# Target.net
KiCad netlist of a schematic drawn in EAGLE
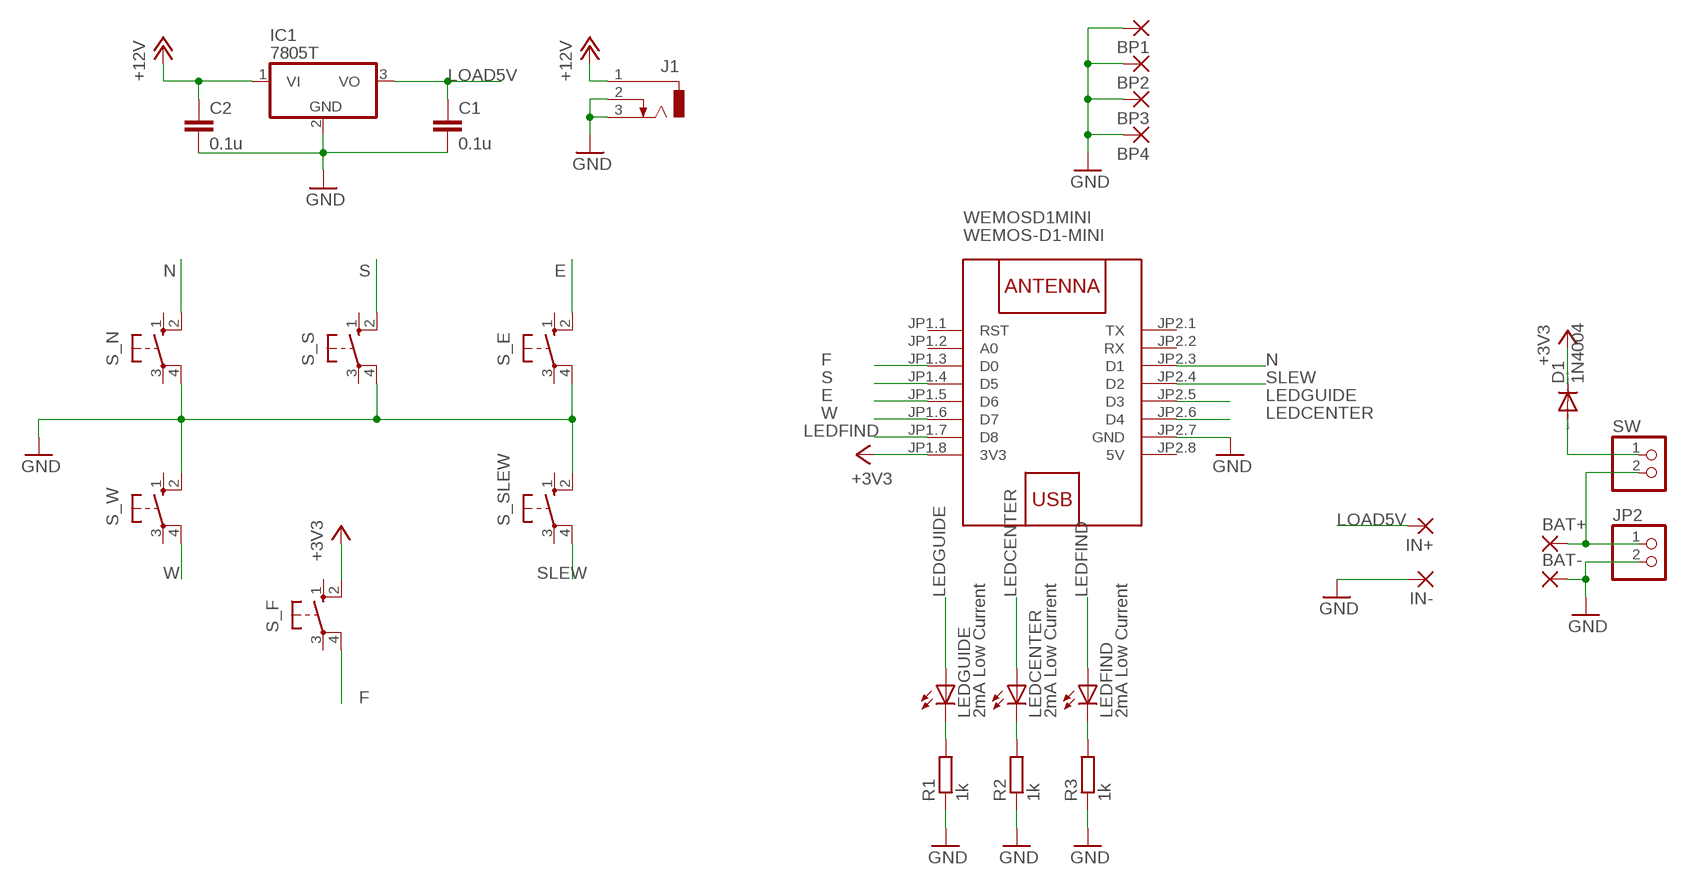
[diagram p0: schematic, sheet 1]

(export (version "E")
  (design (tool "Eeschema 10.0.6"))
  (components
    (comp (ref "BAT+")
      (value "2,15/1,0")
      (footprint "eagle-import:2,15_1,0")
      (libsource (lib "eagle-import") (part "2,15/1,0"))
    )
    (comp (ref "BAT-")
      (value "2,15/1,0")
      (footprint "eagle-import:2,15_1,0")
      (libsource (lib "eagle-import") (part "2,15/1,0"))
    )
    (comp (ref "BP1")
      (value "3,81/1,4")
      (footprint "eagle-import:3,81_1,4")
      (libsource (lib "eagle-import") (part "3,81/1,4"))
    )
    (comp (ref "BP2")
      (value "3,81/1,4")
      (footprint "eagle-import:3,81_1,4")
      (libsource (lib "eagle-import") (part "3,81/1,4"))
    )
    (comp (ref "BP3")
      (value "3,81/1,4")
      (footprint "eagle-import:3,81_1,4")
      (libsource (lib "eagle-import") (part "3,81/1,4"))
    )
    (comp (ref "BP4")
      (value "3,81/1,4")
      (footprint "eagle-import:3,81_1,4")
      (libsource (lib "eagle-import") (part "3,81/1,4"))
    )
    (comp (ref "C1")
      (value "0.1u")
      (footprint "eagle-import:C025_050-025X075")
      (libsource (lib "eagle-import") (part "C-EU025_050-025X075"))
    )
    (comp (ref "C2")
      (value "0.1u")
      (footprint "eagle-import:C025_050-025X075")
      (libsource (lib "eagle-import") (part "C-EU025_050-025X075"))
    )
    (comp (ref "D1")
      (value "1N4004")
      (footprint "eagle-import:DO41-10")
      (libsource (lib "eagle-import") (part "1N4004"))
    )
    (comp (ref "IC1")
      (value "7805T")
      (footprint "eagle-import:TO220H")
      (libsource (lib "eagle-import") (part "78T05"))
    )
    (comp (ref "IN+")
      (value "2,15/1,0")
      (footprint "eagle-import:2,15_1,0")
      (libsource (lib "eagle-import") (part "2,15/1,0"))
    )
    (comp (ref "IN-")
      (value "2,15/1,0")
      (footprint "eagle-import:2,15_1,0")
      (libsource (lib "eagle-import") (part "2,15/1,0"))
    )
    (comp (ref "J1")
      (value "DCJ0303")
      (footprint "eagle-import:DCJ0303")
      (libsource (lib "eagle-import") (part "DCJ0303"))
    )
    (comp (ref "JP2")
      (value "PINHD-1X2")
      (footprint "eagle-import:1X02")
      (libsource (lib "eagle-import") (part "PINHD-1X2"))
    )
    (comp (ref "LEDCENTER")
      (value "2mA Low Current")
      (footprint "eagle-import:LED3MM")
      (libsource (lib "eagle-import") (part "LED3MM"))
    )
    (comp (ref "LEDFIND")
      (value "2mA Low Current")
      (footprint "eagle-import:LED3MM")
      (libsource (lib "eagle-import") (part "LED3MM"))
    )
    (comp (ref "LEDGUIDE")
      (value "2mA Low Current")
      (footprint "eagle-import:LED3MM")
      (libsource (lib "eagle-import") (part "LED3MM"))
    )
    (comp (ref "R1")
      (value "1k")
      (footprint "eagle-import:0204_7")
      (libsource (lib "eagle-import") (part "R-EU_0204/7"))
    )
    (comp (ref "R2")
      (value "1k")
      (footprint "eagle-import:0204_7")
      (libsource (lib "eagle-import") (part "R-EU_0204/7"))
    )
    (comp (ref "R3")
      (value "1k")
      (footprint "eagle-import:0204_7")
      (libsource (lib "eagle-import") (part "R-EU_0204/7"))
    )
    (comp (ref "SW")
      (value "PINHD-1X2")
      (footprint "eagle-import:1X02")
      (libsource (lib "eagle-import") (part "PINHD-1X2"))
    )
    (comp (ref "S_E")
      (value "40-XX")
      (footprint "eagle-import:B3F-40XX")
      (fields (field (name "MF") "OMRON COMPONENTS USA") (field (name "MPN") "B3F-4000"))
      (libsource (lib "eagle-import") (part "40-XX"))
    )
    (comp (ref "S_F")
      (value "40-XX")
      (footprint "eagle-import:B3F-40XX")
      (fields (field (name "MF") "OMRON COMPONENTS USA") (field (name "MPN") "B3F-4000"))
      (libsource (lib "eagle-import") (part "40-XX"))
    )
    (comp (ref "S_N")
      (value "40-XX")
      (footprint "eagle-import:B3F-40XX")
      (fields (field (name "MF") "OMRON COMPONENTS USA") (field (name "MPN") "B3F-4000"))
      (libsource (lib "eagle-import") (part "40-XX"))
    )
    (comp (ref "S_S")
      (value "40-XX")
      (footprint "eagle-import:B3F-40XX")
      (fields (field (name "MF") "OMRON COMPONENTS USA") (field (name "MPN") "B3F-4000"))
      (libsource (lib "eagle-import") (part "40-XX"))
    )
    (comp (ref "S_SLEW")
      (value "40-XX")
      (footprint "eagle-import:B3F-40XX")
      (fields (field (name "MF") "OMRON COMPONENTS USA") (field (name "MPN") "B3F-4000"))
      (libsource (lib "eagle-import") (part "40-XX"))
    )
    (comp (ref "S_W")
      (value "40-XX")
      (footprint "eagle-import:B3F-40XX")
      (fields (field (name "MF") "OMRON COMPONENTS USA") (field (name "MPN") "B3F-4000"))
      (libsource (lib "eagle-import") (part "40-XX"))
    )
    (comp (ref "WEMOSD1MINI")
      (value "WEMOS-D1-MINI")
      (footprint "eagle-import:WEMOS-D1-MINI")
      (libsource (lib "eagle-import") (part "WEMOS-D1-MINI"))
    )
  )
  (nets
    (net (code "1") (name "+3V3") (class "Default")
      (node (ref "D1") (pin "C") (pinfunction "C_C") (pintype "passive"))
      (node (ref "S_F") (pin "2") (pinfunction "S1_2") (pintype "passive"))
      (node (ref "WEMOSD1MINI") (pin "JP1.8") (pinfunction "3V3_JP1.8") (pintype "power_in"))
    )
    (net (code "2") (name "+12V") (class "Default")
      (node (ref "C2") (pin "1") (pinfunction "1_1") (pintype "passive"))
      (node (ref "IC1") (pin "1") (pinfunction "VI_1") (pintype "input"))
      (node (ref "J1") (pin "1") (pinfunction "1_1") (pintype "passive"))
    )
    (net (code "3") (name "/5V") (class "Default")
      (node (ref "WEMOSD1MINI") (pin "JP2.8") (pinfunction "5V_JP2.8") (pintype "power_in"))
    )
    (net (code "4") (name "/E") (class "Default")
      (node (ref "S_E") (pin "2") (pinfunction "S1_2") (pintype "passive"))
      (node (ref "WEMOSD1MINI") (pin "JP1.5") (pinfunction "D6_JP1.5") (pintype "bidirectional"))
    )
    (net (code "5") (name "/F") (class "Default")
      (node (ref "S_F") (pin "4") (pinfunction "P1_4") (pintype "passive"))
      (node (ref "WEMOSD1MINI") (pin "JP1.3") (pinfunction "D0_JP1.3") (pintype "bidirectional"))
    )
    (net (code "6") (name "/LEDCENTER") (class "Default")
      (node (ref "LEDCENTER") (pin "A") (pinfunction "A_A") (pintype "passive"))
      (node (ref "WEMOSD1MINI") (pin "JP2.6") (pinfunction "D4_JP2.6") (pintype "bidirectional"))
    )
    (net (code "7") (name "/LEDFIND") (class "Default")
      (node (ref "LEDFIND") (pin "A") (pinfunction "A_A") (pintype "passive"))
      (node (ref "WEMOSD1MINI") (pin "JP1.7") (pinfunction "D8_JP1.7") (pintype "bidirectional"))
    )
    (net (code "8") (name "/LEDGUIDE") (class "Default")
      (node (ref "LEDGUIDE") (pin "A") (pinfunction "A_A") (pintype "passive"))
      (node (ref "WEMOSD1MINI") (pin "JP2.5") (pinfunction "D3_JP2.5") (pintype "bidirectional"))
    )
    (net (code "9") (name "/LOAD5V") (class "Default")
      (node (ref "C1") (pin "1") (pinfunction "1_1") (pintype "passive"))
      (node (ref "IC1") (pin "3") (pinfunction "VO_3") (pintype "passive"))
      (node (ref "IN+") (pin "1") (pinfunction "P_1") (pintype "passive"))
    )
    (net (code "10") (name "/N") (class "Default")
      (node (ref "S_N") (pin "2") (pinfunction "S1_2") (pintype "passive"))
      (node (ref "WEMOSD1MINI") (pin "JP2.3") (pinfunction "D1_JP2.3") (pintype "bidirectional"))
    )
    (net (code "11") (name "/S") (class "Default")
      (node (ref "S_S") (pin "2") (pinfunction "S1_2") (pintype "passive"))
      (node (ref "WEMOSD1MINI") (pin "JP1.4") (pinfunction "D5_JP1.4") (pintype "bidirectional"))
    )
    (net (code "12") (name "/SLEW") (class "Default")
      (node (ref "S_SLEW") (pin "4") (pinfunction "P1_4") (pintype "passive"))
      (node (ref "WEMOSD1MINI") (pin "JP2.4") (pinfunction "D2_JP2.4") (pintype "bidirectional"))
    )
    (net (code "13") (name "/W") (class "Default")
      (node (ref "S_W") (pin "4") (pinfunction "P1_4") (pintype "passive"))
      (node (ref "WEMOSD1MINI") (pin "JP1.6") (pinfunction "D7_JP1.6") (pintype "bidirectional"))
    )
    (net (code "14") (name "GND") (class "Default")
      (node (ref "BAT-") (pin "1") (pinfunction "P_1") (pintype "passive"))
      (node (ref "BP1") (pin "1") (pinfunction "P_1") (pintype "passive"))
      (node (ref "BP2") (pin "1") (pinfunction "P_1") (pintype "passive"))
      (node (ref "BP3") (pin "1") (pinfunction "P_1") (pintype "passive"))
      (node (ref "BP4") (pin "1") (pinfunction "P_1") (pintype "passive"))
      (node (ref "C1") (pin "2") (pinfunction "2_2") (pintype "passive"))
      (node (ref "C2") (pin "2") (pinfunction "2_2") (pintype "passive"))
      (node (ref "IC1") (pin "2") (pinfunction "GND_2") (pintype "passive"))
      (node (ref "IN-") (pin "1") (pinfunction "P_1") (pintype "passive"))
      (node (ref "J1") (pin "2") (pinfunction "2_2") (pintype "passive"))
      (node (ref "J1") (pin "3") (pinfunction "3_3") (pintype "passive"))
      (node (ref "JP2") (pin "2") (pinfunction "2_2") (pintype "passive"))
      (node (ref "R1") (pin "1") (pinfunction "1_1") (pintype "passive"))
      (node (ref "R2") (pin "1") (pinfunction "1_1") (pintype "passive"))
      (node (ref "R3") (pin "1") (pinfunction "1_1") (pintype "passive"))
      (node (ref "S_E") (pin "4") (pinfunction "P1_4") (pintype "passive"))
      (node (ref "S_N") (pin "4") (pinfunction "P1_4") (pintype "passive"))
      (node (ref "S_S") (pin "4") (pinfunction "P1_4") (pintype "passive"))
      (node (ref "S_SLEW") (pin "2") (pinfunction "S1_2") (pintype "passive"))
      (node (ref "S_W") (pin "2") (pinfunction "S1_2") (pintype "passive"))
      (node (ref "WEMOSD1MINI") (pin "JP2.7") (pinfunction "GND_JP2.7") (pintype "power_in"))
    )
    (net (code "15") (name "Net-(BAT+-P)") (class "Default")
      (node (ref "BAT+") (pin "1") (pinfunction "P_1") (pintype "passive"))
      (node (ref "JP2") (pin "1") (pinfunction "1_1") (pintype "passive"))
      (node (ref "SW") (pin "2") (pinfunction "2_2") (pintype "passive"))
    )
    (net (code "16") (name "Net-(D1-PadA)") (class "Default")
      (node (ref "D1") (pin "A") (pinfunction "A_A") (pintype "passive"))
      (node (ref "SW") (pin "1") (pinfunction "1_1") (pintype "passive"))
    )
    (net (code "17") (name "Net-(LEDCENTER-C)") (class "Default")
      (node (ref "LEDCENTER") (pin "K") (pinfunction "C_K") (pintype "passive"))
      (node (ref "R2") (pin "2") (pinfunction "2_2") (pintype "passive"))
    )
    (net (code "18") (name "Net-(LEDFIND-C)") (class "Default")
      (node (ref "LEDFIND") (pin "K") (pinfunction "C_K") (pintype "passive"))
      (node (ref "R3") (pin "2") (pinfunction "2_2") (pintype "passive"))
    )
    (net (code "19") (name "Net-(LEDGUIDE-C)") (class "Default")
      (node (ref "LEDGUIDE") (pin "K") (pinfunction "C_K") (pintype "passive"))
      (node (ref "R1") (pin "2") (pinfunction "2_2") (pintype "passive"))
    )
    (net (code "20") (name "unconnected-(S_E-P-Pad3)") (class "Default")
      (node (ref "S_E") (pin "3") (pinfunction "P_3") (pintype "passive"))
    )
    (net (code "21") (name "unconnected-(S_E-S-Pad1)") (class "Default")
      (node (ref "S_E") (pin "1") (pinfunction "S_1") (pintype "passive"))
    )
    (net (code "22") (name "unconnected-(S_F-P-Pad3)") (class "Default")
      (node (ref "S_F") (pin "3") (pinfunction "P_3") (pintype "passive"))
    )
    (net (code "23") (name "unconnected-(S_F-S-Pad1)") (class "Default")
      (node (ref "S_F") (pin "1") (pinfunction "S_1") (pintype "passive"))
    )
    (net (code "24") (name "unconnected-(S_N-P-Pad3)") (class "Default")
      (node (ref "S_N") (pin "3") (pinfunction "P_3") (pintype "passive"))
    )
    (net (code "25") (name "unconnected-(S_N-S-Pad1)") (class "Default")
      (node (ref "S_N") (pin "1") (pinfunction "S_1") (pintype "passive"))
    )
    (net (code "26") (name "unconnected-(S_S-P-Pad3)") (class "Default")
      (node (ref "S_S") (pin "3") (pinfunction "P_3") (pintype "passive"))
    )
    (net (code "27") (name "unconnected-(S_S-S-Pad1)") (class "Default")
      (node (ref "S_S") (pin "1") (pinfunction "S_1") (pintype "passive"))
    )
    (net (code "28") (name "unconnected-(S_SLEW-P-Pad3)") (class "Default")
      (node (ref "S_SLEW") (pin "3") (pinfunction "P_3") (pintype "passive"))
    )
    (net (code "29") (name "unconnected-(S_SLEW-S-Pad1)") (class "Default")
      (node (ref "S_SLEW") (pin "1") (pinfunction "S_1") (pintype "passive"))
    )
    (net (code "30") (name "unconnected-(S_W-P-Pad3)") (class "Default")
      (node (ref "S_W") (pin "3") (pinfunction "P_3") (pintype "passive"))
    )
    (net (code "31") (name "unconnected-(S_W-S-Pad1)") (class "Default")
      (node (ref "S_W") (pin "1") (pinfunction "S_1") (pintype "passive"))
    )
    (net (code "32") (name "unconnected-(WEMOSD1MINI-A0-PadJP1.2)") (class "Default")
      (node (ref "WEMOSD1MINI") (pin "JP1.2") (pinfunction "A0_JP1.2") (pintype "bidirectional"))
    )
    (net (code "33") (name "unconnected-(WEMOSD1MINI-RST-PadJP1.1)") (class "Default")
      (node (ref "WEMOSD1MINI") (pin "JP1.1") (pinfunction "RST_JP1.1") (pintype "bidirectional"))
    )
    (net (code "34") (name "unconnected-(WEMOSD1MINI-RX-PadJP2.2)") (class "Default")
      (node (ref "WEMOSD1MINI") (pin "JP2.2") (pinfunction "RX_JP2.2") (pintype "bidirectional"))
    )
    (net (code "35") (name "unconnected-(WEMOSD1MINI-TX-PadJP2.1)") (class "Default")
      (node (ref "WEMOSD1MINI") (pin "JP2.1") (pinfunction "TX_JP2.1") (pintype "bidirectional"))
    )
  )
)
